# SDS011.net
KiCad netlist of a schematic drawn in EAGLE
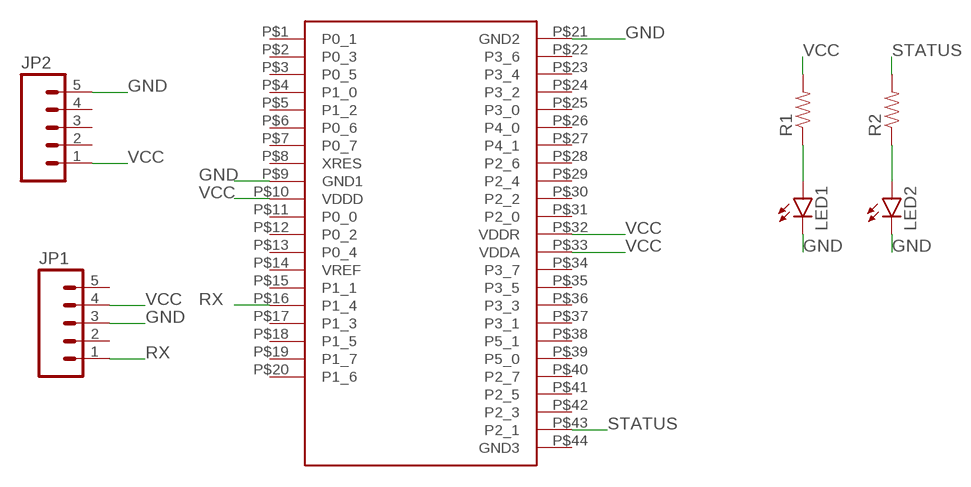
[diagram p0: schematic, sheet 1]

(export (version "E")
  (design (tool "Eeschema 10.0.6"))
  (components
    (comp (ref "JP1")
      (value "M05PTH_LONGPADS")
      (footprint "eagle-import:1X05_LONGPADS")
      (libsource (lib "eagle-import") (part "M05PTH_LONGPADS"))
    )
    (comp (ref "JP2")
      (value "M05PTH_LONGPADS")
      (footprint "eagle-import:1X05_LONGPADS")
      (libsource (lib "eagle-import") (part "M05PTH_LONGPADS"))
    )
    (comp (ref "LED1")
      (value "LED3MM")
      (footprint "eagle-import:LED3MM")
      (libsource (lib "eagle-import") (part "LED3MM"))
    )
    (comp (ref "LED2")
      (value "LED3MM")
      (footprint "eagle-import:LED3MM")
      (libsource (lib "eagle-import") (part "LED3MM"))
    )
    (comp (ref "R1")
      (value "RESISTORPTH-1/4W")
      (footprint "eagle-import:AXIAL-0.4")
      (libsource (lib "eagle-import") (part "RESISTORPTH-1/4W"))
    )
    (comp (ref "R2")
      (value "RESISTORPTH-1/4W")
      (footprint "eagle-import:AXIAL-0.4")
      (libsource (lib "eagle-import") (part "RESISTORPTH-1/4W"))
    )
    (comp (ref "U$1")
      (value "CYBLE_MODULE")
      (footprint "eagle-import:CYBLE_MODULE")
      (libsource (lib "eagle-import") (part "CYBLE_MODULE"))
    )
  )
  (nets
    (net (code "1") (name "/GND") (class "Default")
      (node (ref "JP1") (pin "3") (pinfunction "3_3") (pintype "passive"))
      (node (ref "JP2") (pin "5") (pinfunction "5_5") (pintype "passive"))
      (node (ref "LED1") (pin "K") (pinfunction "C_K") (pintype "passive"))
      (node (ref "LED2") (pin "K") (pinfunction "C_K") (pintype "passive"))
      (node (ref "U$1") (pin "P$21") (pinfunction "GND2_P$21") (pintype "bidirectional"))
      (node (ref "U$1") (pin "P$9") (pinfunction "GND1_P$9") (pintype "bidirectional"))
    )
    (net (code "2") (name "/RX") (class "Default")
      (node (ref "JP1") (pin "1") (pinfunction "1_1") (pintype "passive"))
      (node (ref "U$1") (pin "P$16") (pinfunction "P1_4_P$16") (pintype "bidirectional"))
    )
    (net (code "3") (name "/STATUS") (class "Default")
      (node (ref "R2") (pin "P$2") (pinfunction "2_P$2") (pintype "passive"))
      (node (ref "U$1") (pin "P$43") (pinfunction "P2_1_P$43") (pintype "bidirectional"))
    )
    (net (code "4") (name "/VCC") (class "Default")
      (node (ref "JP1") (pin "4") (pinfunction "4_4") (pintype "passive"))
      (node (ref "JP2") (pin "1") (pinfunction "1_1") (pintype "passive"))
      (node (ref "R1") (pin "P$2") (pinfunction "2_P$2") (pintype "passive"))
      (node (ref "U$1") (pin "P$10") (pinfunction "VDDD_P$10") (pintype "bidirectional"))
      (node (ref "U$1") (pin "P$32") (pinfunction "VDDR_P$32") (pintype "bidirectional"))
      (node (ref "U$1") (pin "P$33") (pinfunction "VDDA_P$33") (pintype "bidirectional"))
    )
    (net (code "5") (name "Net-(R1-1)") (class "Default")
      (node (ref "LED1") (pin "A") (pinfunction "A_A") (pintype "passive"))
      (node (ref "R1") (pin "P$1") (pinfunction "1_P$1") (pintype "passive"))
    )
    (net (code "6") (name "Net-(R2-1)") (class "Default")
      (node (ref "LED2") (pin "A") (pinfunction "A_A") (pintype "passive"))
      (node (ref "R2") (pin "P$1") (pinfunction "1_P$1") (pintype "passive"))
    )
    (net (code "7") (name "unconnected-(JP1-Pad2)") (class "Default")
      (node (ref "JP1") (pin "2") (pinfunction "2_2") (pintype "passive"))
    )
    (net (code "8") (name "unconnected-(JP1-Pad5)") (class "Default")
      (node (ref "JP1") (pin "5") (pinfunction "5_5") (pintype "passive"))
    )
    (net (code "9") (name "unconnected-(JP2-Pad2)") (class "Default")
      (node (ref "JP2") (pin "2") (pinfunction "2_2") (pintype "passive"))
    )
    (net (code "10") (name "unconnected-(JP2-Pad3)") (class "Default")
      (node (ref "JP2") (pin "3") (pinfunction "3_3") (pintype "passive"))
    )
    (net (code "11") (name "unconnected-(JP2-Pad4)") (class "Default")
      (node (ref "JP2") (pin "4") (pinfunction "4_4") (pintype "passive"))
    )
    (net (code "12") (name "unconnected-(U$1-GND3-PadP$44)") (class "Default")
      (node (ref "U$1") (pin "P$44") (pinfunction "GND3_P$44") (pintype "bidirectional"))
    )
    (net (code "13") (name "unconnected-(U$1-P0_0-PadP$11)") (class "Default")
      (node (ref "U$1") (pin "P$11") (pinfunction "P0_0_P$11") (pintype "bidirectional"))
    )
    (net (code "14") (name "unconnected-(U$1-P0_1-PadP$1)") (class "Default")
      (node (ref "U$1") (pin "P$1") (pinfunction "P0_1_P$1") (pintype "bidirectional"))
    )
    (net (code "15") (name "unconnected-(U$1-P0_2-PadP$12)") (class "Default")
      (node (ref "U$1") (pin "P$12") (pinfunction "P0_2_P$12") (pintype "bidirectional"))
    )
    (net (code "16") (name "unconnected-(U$1-P0_3-PadP$2)") (class "Default")
      (node (ref "U$1") (pin "P$2") (pinfunction "P0_3_P$2") (pintype "bidirectional"))
    )
    (net (code "17") (name "unconnected-(U$1-P0_4-PadP$13)") (class "Default")
      (node (ref "U$1") (pin "P$13") (pinfunction "P0_4_P$13") (pintype "bidirectional"))
    )
    (net (code "18") (name "unconnected-(U$1-P0_5-PadP$3)") (class "Default")
      (node (ref "U$1") (pin "P$3") (pinfunction "P0_5_P$3") (pintype "bidirectional"))
    )
    (net (code "19") (name "unconnected-(U$1-P0_6-PadP$6)") (class "Default")
      (node (ref "U$1") (pin "P$6") (pinfunction "P0_6_P$6") (pintype "bidirectional"))
    )
    (net (code "20") (name "unconnected-(U$1-P0_7-PadP$7)") (class "Default")
      (node (ref "U$1") (pin "P$7") (pinfunction "P0_7_P$7") (pintype "bidirectional"))
    )
    (net (code "21") (name "unconnected-(U$1-P1_0-PadP$4)") (class "Default")
      (node (ref "U$1") (pin "P$4") (pinfunction "P1_0_P$4") (pintype "bidirectional"))
    )
    (net (code "22") (name "unconnected-(U$1-P1_1-PadP$15)") (class "Default")
      (node (ref "U$1") (pin "P$15") (pinfunction "P1_1_P$15") (pintype "bidirectional"))
    )
    (net (code "23") (name "unconnected-(U$1-P1_2-PadP$5)") (class "Default")
      (node (ref "U$1") (pin "P$5") (pinfunction "P1_2_P$5") (pintype "bidirectional"))
    )
    (net (code "24") (name "unconnected-(U$1-P1_3-PadP$17)") (class "Default")
      (node (ref "U$1") (pin "P$17") (pinfunction "P1_3_P$17") (pintype "bidirectional"))
    )
    (net (code "25") (name "unconnected-(U$1-P1_5-PadP$18)") (class "Default")
      (node (ref "U$1") (pin "P$18") (pinfunction "P1_5_P$18") (pintype "bidirectional"))
    )
    (net (code "26") (name "unconnected-(U$1-P1_6-PadP$20)") (class "Default")
      (node (ref "U$1") (pin "P$20") (pinfunction "P1_6_P$20") (pintype "bidirectional"))
    )
    (net (code "27") (name "unconnected-(U$1-P1_7-PadP$19)") (class "Default")
      (node (ref "U$1") (pin "P$19") (pinfunction "P1_7_P$19") (pintype "bidirectional"))
    )
    (net (code "28") (name "unconnected-(U$1-P2_0-PadP$31)") (class "Default")
      (node (ref "U$1") (pin "P$31") (pinfunction "P2_0_P$31") (pintype "bidirectional"))
    )
    (net (code "29") (name "unconnected-(U$1-P2_2-PadP$30)") (class "Default")
      (node (ref "U$1") (pin "P$30") (pinfunction "P2_2_P$30") (pintype "bidirectional"))
    )
    (net (code "30") (name "unconnected-(U$1-P2_3-PadP$42)") (class "Default")
      (node (ref "U$1") (pin "P$42") (pinfunction "P2_3_P$42") (pintype "bidirectional"))
    )
    (net (code "31") (name "unconnected-(U$1-P2_4-PadP$29)") (class "Default")
      (node (ref "U$1") (pin "P$29") (pinfunction "P2_4_P$29") (pintype "bidirectional"))
    )
    (net (code "32") (name "unconnected-(U$1-P2_5-PadP$41)") (class "Default")
      (node (ref "U$1") (pin "P$41") (pinfunction "P2_5_P$41") (pintype "bidirectional"))
    )
    (net (code "33") (name "unconnected-(U$1-P2_6-PadP$28)") (class "Default")
      (node (ref "U$1") (pin "P$28") (pinfunction "P2_6_P$28") (pintype "bidirectional"))
    )
    (net (code "34") (name "unconnected-(U$1-P2_7-PadP$40)") (class "Default")
      (node (ref "U$1") (pin "P$40") (pinfunction "P2_7_P$40") (pintype "bidirectional"))
    )
    (net (code "35") (name "unconnected-(U$1-P3_0-PadP$25)") (class "Default")
      (node (ref "U$1") (pin "P$25") (pinfunction "P3_0_P$25") (pintype "bidirectional"))
    )
    (net (code "36") (name "unconnected-(U$1-P3_1-PadP$37)") (class "Default")
      (node (ref "U$1") (pin "P$37") (pinfunction "P3_1_P$37") (pintype "bidirectional"))
    )
    (net (code "37") (name "unconnected-(U$1-P3_2-PadP$24)") (class "Default")
      (node (ref "U$1") (pin "P$24") (pinfunction "P3_2_P$24") (pintype "bidirectional"))
    )
    (net (code "38") (name "unconnected-(U$1-P3_3-PadP$36)") (class "Default")
      (node (ref "U$1") (pin "P$36") (pinfunction "P3_3_P$36") (pintype "bidirectional"))
    )
    (net (code "39") (name "unconnected-(U$1-P3_4-PadP$23)") (class "Default")
      (node (ref "U$1") (pin "P$23") (pinfunction "P3_4_P$23") (pintype "bidirectional"))
    )
    (net (code "40") (name "unconnected-(U$1-P3_5-PadP$35)") (class "Default")
      (node (ref "U$1") (pin "P$35") (pinfunction "P3_5_P$35") (pintype "bidirectional"))
    )
    (net (code "41") (name "unconnected-(U$1-P3_6-PadP$22)") (class "Default")
      (node (ref "U$1") (pin "P$22") (pinfunction "P3_6_P$22") (pintype "bidirectional"))
    )
    (net (code "42") (name "unconnected-(U$1-P3_7-PadP$34)") (class "Default")
      (node (ref "U$1") (pin "P$34") (pinfunction "P3_7_P$34") (pintype "bidirectional"))
    )
    (net (code "43") (name "unconnected-(U$1-P4_0-PadP$26)") (class "Default")
      (node (ref "U$1") (pin "P$26") (pinfunction "P4_0_P$26") (pintype "bidirectional"))
    )
    (net (code "44") (name "unconnected-(U$1-P4_1-PadP$27)") (class "Default")
      (node (ref "U$1") (pin "P$27") (pinfunction "P4_1_P$27") (pintype "bidirectional"))
    )
    (net (code "45") (name "unconnected-(U$1-P5_0-PadP$39)") (class "Default")
      (node (ref "U$1") (pin "P$39") (pinfunction "P5_0_P$39") (pintype "bidirectional"))
    )
    (net (code "46") (name "unconnected-(U$1-P5_1-PadP$38)") (class "Default")
      (node (ref "U$1") (pin "P$38") (pinfunction "P5_1_P$38") (pintype "bidirectional"))
    )
    (net (code "47") (name "unconnected-(U$1-VREF-PadP$14)") (class "Default")
      (node (ref "U$1") (pin "P$14") (pinfunction "VREF_P$14") (pintype "bidirectional"))
    )
    (net (code "48") (name "unconnected-(U$1-XRES-PadP$8)") (class "Default")
      (node (ref "U$1") (pin "P$8") (pinfunction "XRES_P$8") (pintype "bidirectional"))
    )
  )
)
